# Sheet1.net
KiCad netlist of a schematic drawn in Altium Designer
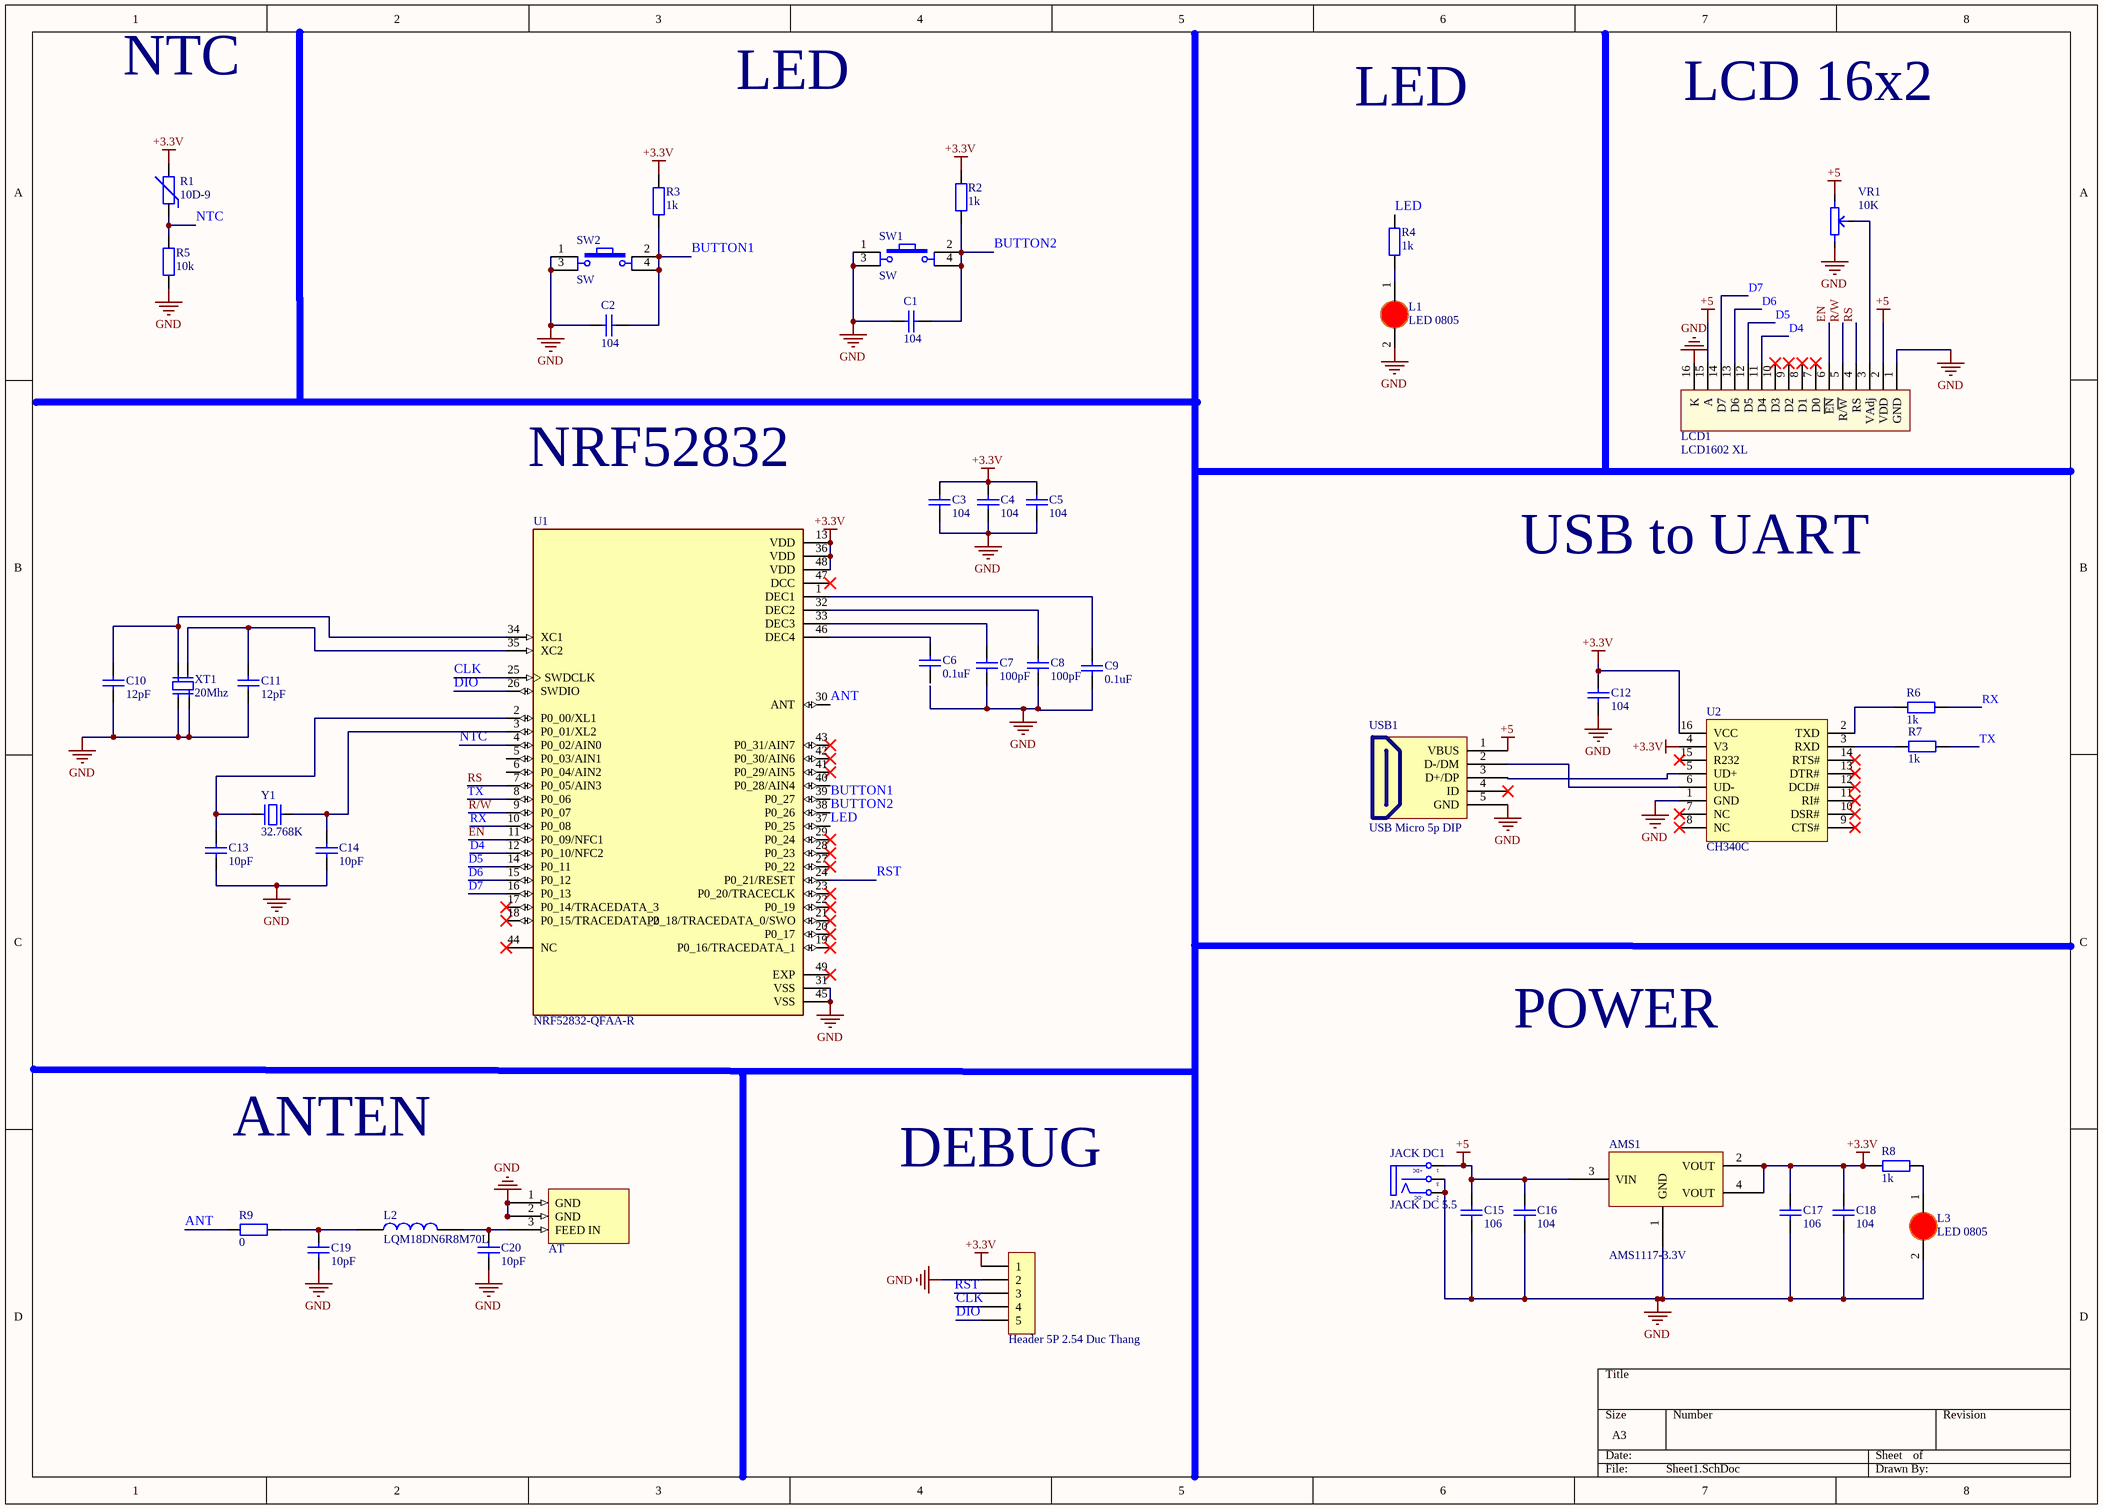
[diagram p0: Sheet1.SchDoc]

(export (version "E")
  (design (tool "Eeschema 10.0.6"))
  (components
    (comp (ref "AMS1")
      (value "AMS1117-3.3V")
      (footprint "SOT223")
      (description "Dán")
      (libsource (lib "Altium_Lib_by_KhueNguyenCreator") (part "AMS1117 SMD"))
    )
    (comp (ref "AT")
      (value "ANTEN")
      (footprint "Anten IFA")
      (description "Anten IFA- BLE RANGDONG")
      (libsource (lib "Altium_Lib_by_KhueNguyenCreator") (part "ANTEN"))
    )
    (comp (ref "C1")
      (value "104")
      (footprint "tu 0603")
      (description "Dán")
      (libsource (lib "Altium_Lib_by_KhueNguyenCreator") (part "Tu 0603 102 50V 10%"))
    )
    (comp (ref "C2")
      (value "104")
      (footprint "tu 0603")
      (description "Dán")
      (libsource (lib "Altium_Lib_by_KhueNguyenCreator") (part "Tu 0603 102 50V 10%"))
    )
    (comp (ref "C3")
      (value "104")
      (footprint "tu 0603")
      (description "Dán")
      (libsource (lib "Altium_Lib_by_KhueNguyenCreator") (part "Tu 0603 102 50V 10%"))
    )
    (comp (ref "C4")
      (value "104")
      (footprint "tu 0603")
      (description "Dán")
      (libsource (lib "Altium_Lib_by_KhueNguyenCreator") (part "Tu 0603 102 50V 10%"))
    )
    (comp (ref "C5")
      (value "104")
      (footprint "tu 0603")
      (description "Dán")
      (libsource (lib "Altium_Lib_by_KhueNguyenCreator") (part "Tu 0603 102 50V 10%"))
    )
    (comp (ref "C6")
      (value "0.1uF")
      (footprint "tu 0603")
      (description "Dán")
      (libsource (lib "Altium_Lib_by_KhueNguyenCreator") (part "Tu 0603 102 50V 10%"))
    )
    (comp (ref "C7")
      (value "100pF")
      (footprint "tu 0603")
      (description "Dán")
      (libsource (lib "Altium_Lib_by_KhueNguyenCreator") (part "Tu 0603 102 50V 10%"))
    )
    (comp (ref "C8")
      (value "100pF")
      (footprint "tu 0603")
      (description "Dán")
      (libsource (lib "Altium_Lib_by_KhueNguyenCreator") (part "Tu 0603 102 50V 10%"))
    )
    (comp (ref "C9")
      (value "0.1uF")
      (footprint "tu 0603")
      (description "Dán")
      (libsource (lib "Altium_Lib_by_KhueNguyenCreator") (part "Tu 0603 102 50V 10%"))
    )
    (comp (ref "C10")
      (value "12pF")
      (footprint "tu 0603")
      (description "Dán")
      (libsource (lib "Altium_Lib_by_KhueNguyenCreator") (part "Tu 0603 102 50V 10%"))
    )
    (comp (ref "C11")
      (value "12pF")
      (footprint "tu 0603")
      (description "Dán")
      (libsource (lib "Altium_Lib_by_KhueNguyenCreator") (part "Tu 0603 102 50V 10%"))
    )
    (comp (ref "C12")
      (value "104")
      (footprint "tu 0603")
      (description "Dán")
      (libsource (lib "Altium_Lib_by_KhueNguyenCreator") (part "Tu 0603 104 50V 10%"))
    )
    (comp (ref "C13")
      (value "10pF")
      (footprint "tu 0603")
      (description "Dán")
      (libsource (lib "Altium_Lib_by_KhueNguyenCreator") (part "Tu 0603 102 50V 10%"))
    )
    (comp (ref "C14")
      (value "10pF")
      (footprint "tu 0603")
      (description "Dán")
      (libsource (lib "Altium_Lib_by_KhueNguyenCreator") (part "Tu 0603 102 50V 10%"))
    )
    (comp (ref "C15")
      (value "106")
      (footprint "tu 0603")
      (description "Dán")
      (libsource (lib "Altium_Lib_by_KhueNguyenCreator") (part "Tu 0603 106 16V 20%"))
    )
    (comp (ref "C16")
      (value "104")
      (footprint "tu 0603")
      (description "Dán")
      (libsource (lib "Altium_Lib_by_KhueNguyenCreator") (part "Tu 0603 104 50V 10%"))
    )
    (comp (ref "C17")
      (value "106")
      (footprint "tu 0603")
      (description "Dán")
      (libsource (lib "Altium_Lib_by_KhueNguyenCreator") (part "Tu 0603 106 16V 20%"))
    )
    (comp (ref "C18")
      (value "104")
      (footprint "tu 0603")
      (description "Dán")
      (libsource (lib "Altium_Lib_by_KhueNguyenCreator") (part "Tu 0603 104 50V 10%"))
    )
    (comp (ref "C19")
      (value "10pF")
      (footprint "tu 0603")
      (description "Dán")
      (libsource (lib "Altium_Lib_by_KhueNguyenCreator") (part "Tu 0603 102 50V 10%"))
    )
    (comp (ref "C20")
      (value "10pF")
      (footprint "tu 0603")
      (description "Dán")
      (libsource (lib "Altium_Lib_by_KhueNguyenCreator") (part "Tu 0603 102 50V 10%"))
    )
    (comp (ref "H1")
      (value "Header 5P 2.54 Duc Thang")
      (footprint "XH2.54M-5")
      (description "Cắm")
      (libsource (lib "Altium_Lib_by_KhueNguyenCreator") (part "Header 5P 2.54 Duc Thang"))
    )
    (comp (ref "JACK DC1")
      (value "JACK DC 5.5")
      (footprint "JACK DC 5.5")
      (libsource (lib "Altium_Lib_by_KhueNguyenCreator") (part "JACK DC 5.5"))
    )
    (comp (ref "L1")
      (value "LED 0805")
      (footprint "LED-0805-Red")
      (description "Dán")
      (libsource (lib "Altium_Lib_by_KhueNguyenCreator") (part "LED 0805 Do"))
    )
    (comp (ref "L2")
      (value "LQM18DN6R8M70L")
      (footprint "INDC1608X95N")
      (description "Inductor with Inductance 6.8uH Tol.+/-20% Package 0603 (1608)")
      (fields (field (name "MF") "Murata Electronics"))
      (libsource (lib "cuon_cam_0603") (part "LQM18DN6R8M70L"))
    )
    (comp (ref "L3")
      (value "LED 0805")
      (footprint "LED-0805-Red")
      (description "Dán")
      (libsource (lib "Altium_Lib_by_KhueNguyenCreator") (part "LED 0805 Do"))
    )
    (comp (ref "LCD1")
      (value "LCD1602 XL")
      (footprint "LCD1602 with Jump")
      (description "LCD 1602 Xanh Lá")
      (libsource (lib "Altium_Lib_by_KhueNguyenCreator") (part "LCD1602 XL"))
    )
    (comp (ref "R1")
      (value "10D-9")
      (footprint "tro nhiet d-9")
      (description "Cắm")
      (libsource (lib "Altium_Lib_by_KhueNguyenCreator") (part "Tro Nhiet NTC 10D-9"))
    )
    (comp (ref "R2")
      (value "1k")
      (footprint "tro smd 0603")
      (description "Dán")
      (libsource (lib "Altium_Lib_by_KhueNguyenCreator") (part "Tro 0603 1% 1k"))
    )
    (comp (ref "R3")
      (value "1k")
      (footprint "tro smd 0603")
      (description "Dán")
      (libsource (lib "Altium_Lib_by_KhueNguyenCreator") (part "Tro 0603 1% 1k"))
    )
    (comp (ref "R4")
      (value "1k")
      (footprint "tro smd 0603")
      (description "Dán")
      (libsource (lib "Altium_Lib_by_KhueNguyenCreator") (part "Tro 0603 1% 1k"))
    )
    (comp (ref "R5")
      (value "10k")
      (footprint "tro smd 0603")
      (description "Dán")
      (libsource (lib "Altium_Lib_by_KhueNguyenCreator") (part "Tro 0603 1% 1k"))
    )
    (comp (ref "R6")
      (value "1k")
      (footprint "tro smd 0603")
      (description "Dán")
      (libsource (lib "Altium_Lib_by_KhueNguyenCreator") (part "Tro 0603 1% 1k"))
    )
    (comp (ref "R7")
      (value "1k")
      (footprint "tro smd 0603")
      (description "Dán")
      (libsource (lib "Altium_Lib_by_KhueNguyenCreator") (part "Tro 0603 1% 1k"))
    )
    (comp (ref "R8")
      (value "1k")
      (footprint "tro smd 0603")
      (description "Dán")
      (libsource (lib "Altium_Lib_by_KhueNguyenCreator") (part "Tro 0603 1% 1k"))
    )
    (comp (ref "R9")
      (value "0")
      (footprint "tro smd 0603")
      (description "Dán")
      (libsource (lib "Altium_Lib_by_KhueNguyenCreator") (part "Tro 0603 1% 1k"))
    )
    (comp (ref "SW1")
      (value "SW")
      (footprint "SW4")
      (description "Switch button 4 pin")
      (libsource (lib "syhaunguyen") (part "SW4"))
    )
    (comp (ref "SW2")
      (value "SW")
      (footprint "SW4")
      (description "Switch button 4 pin")
      (libsource (lib "syhaunguyen") (part "SW4"))
    )
    (comp (ref "U1")
      (value "NRF52832-QFAA-R")
      (footprint "QFN40P600X600X90-49N")
      (description "IC RF TxRx + MCU Bluetooth, General ISM > 1GHz ANT, Bluetooth v5.0 2.4GHz 48-VFQFN Exposed Pad")
      (fields (field (name "MF") "Nordic"))
      (libsource (lib "NRF52832-QFAA-R") (part "NRF52832-QFAA-R"))
    )
    (comp (ref "U2")
      (value "CH340C")
      (footprint "SOIC16_50_284_25X90_SMT")
      (description "USB Bridge, USB to UART USB 2.0 UART Interface")
      (fields (field (name "MANUFACTURER") "Olimex"))
      (libsource (lib "Altium_Lib_by_KhueNguyenCreator") (part "CH340C"))
    )
    (comp (ref "USB1")
      (value "USB Micro 5p DIP")
      (footprint "USB Micro 5p DIP")
      (description "USB Type B")
      (libsource (lib "Altium_Lib_by_KhueNguyenCreator") (part "USB Micro 5p DIP"))
    )
    (comp (ref "VR1")
      (value "10K")
      (footprint "Bien Tro Tam Giac Dung")
      (description "Cắm")
      (libsource (lib "Altium_Lib_by_KhueNguyenCreator") (part "Bien tro tam giac 10K Dung"))
    )
    (comp (ref "XT1")
      (value "20Mhz")
      (footprint "Thach Anh 4 chan 1")
      (description "Crystal For all Crystal 2pin.")
      (libsource (lib "Altium_Lib_by_KhueNguyenCreator") (part "Thach Anh 4 Chan SMD"))
    )
    (comp (ref "Y1")
      (value "32.768K")
      (footprint "Thach Anh 2 chan SMD5032")
      (description "Crystal For all Crystal 2pin.")
      (libsource (lib "Altium_Lib_by_KhueNguyenCreator") (part "Thach Anh 2 chan SMD 5032"))
    )
  )
  (nets
    (net (code "1") (name "+3.3V") (class "Default")
      (node (ref "AMS1") (pin "2") (pinfunction "VOUT_2") (pintype "passive"))
      (node (ref "AMS1") (pin "4") (pinfunction "VOUT_4") (pintype "passive"))
      (node (ref "C12") (pin "1") (pinfunction "1_1") (pintype "passive"))
      (node (ref "C17") (pin "1") (pinfunction "1_1") (pintype "passive"))
      (node (ref "C18") (pin "1") (pinfunction "1_1") (pintype "passive"))
      (node (ref "C3") (pin "1") (pinfunction "1_1") (pintype "passive"))
      (node (ref "C4") (pin "1") (pinfunction "1_1") (pintype "passive"))
      (node (ref "C5") (pin "1") (pinfunction "1_1") (pintype "passive"))
      (node (ref "H1") (pin "1") (pinfunction "1_1") (pintype "passive"))
      (node (ref "R1") (pin "2") (pinfunction "2_2") (pintype "passive"))
      (node (ref "R2") (pin "2") (pinfunction "2_2") (pintype "passive"))
      (node (ref "R3") (pin "2") (pinfunction "2_2") (pintype "passive"))
      (node (ref "R8") (pin "1") (pinfunction "1_1") (pintype "passive"))
      (node (ref "U1") (pin "13") (pinfunction "VDD_13") (pintype "power_in"))
      (node (ref "U1") (pin "36") (pinfunction "VDD_36") (pintype "power_in"))
      (node (ref "U1") (pin "48") (pinfunction "VDD_48") (pintype "power_in"))
      (node (ref "U2") (pin "16") (pinfunction "VCC_16") (pintype "passive"))
      (node (ref "U2") (pin "4") (pinfunction "V3_4") (pintype "passive"))
    )
    (net (code "2") (name "+5") (class "Default")
      (node (ref "AMS1") (pin "3") (pinfunction "VIN_3") (pintype "passive"))
      (node (ref "C15") (pin "1") (pinfunction "1_1") (pintype "passive"))
      (node (ref "C16") (pin "1") (pinfunction "1_1") (pintype "passive"))
      (node (ref "JACK DC1") (pin "1") (pinfunction "T_1") (pintype "passive"))
      (node (ref "LCD1") (pin "15") (pinfunction "A_15") (pintype "passive"))
      (node (ref "LCD1") (pin "2") (pinfunction "VDD_2") (pintype "passive"))
      (node (ref "USB1") (pin "1") (pinfunction "VBUS_1") (pintype "passive"))
      (node (ref "VR1") (pin "1") (pinfunction "1_1") (pintype "passive"))
    )
    (net (code "3") (name "/ANT") (class "Default")
      (node (ref "R9") (pin "1") (pinfunction "1_1") (pintype "passive"))
      (node (ref "U1") (pin "30") (pinfunction "ANT_30") (pintype "bidirectional"))
    )
    (net (code "4") (name "/BUTTON1") (class "Default")
      (node (ref "C2") (pin "2") (pinfunction "2_2") (pintype "passive"))
      (node (ref "R3") (pin "1") (pinfunction "1_1") (pintype "passive"))
      (node (ref "SW2") (pin "2") (pintype "passive"))
      (node (ref "SW2") (pin "4") (pintype "passive"))
      (node (ref "U1") (pin "39") (pinfunction "P0_27_39") (pintype "bidirectional"))
    )
    (net (code "5") (name "/BUTTON2") (class "Default")
      (node (ref "C1") (pin "2") (pinfunction "2_2") (pintype "passive"))
      (node (ref "R2") (pin "1") (pinfunction "1_1") (pintype "passive"))
      (node (ref "SW1") (pin "2") (pintype "passive"))
      (node (ref "SW1") (pin "4") (pintype "passive"))
      (node (ref "U1") (pin "38") (pinfunction "P0_26_38") (pintype "bidirectional"))
    )
    (net (code "6") (name "/CLK") (class "Default")
      (node (ref "H1") (pin "4") (pinfunction "4_4") (pintype "passive"))
      (node (ref "U1") (pin "25") (pinfunction "SWDCLK_25") (pintype "input"))
    )
    (net (code "7") (name "/D4") (class "Default")
      (node (ref "LCD1") (pin "11") (pinfunction "D4_11") (pintype "passive"))
      (node (ref "U1") (pin "12") (pinfunction "P0_10/NFC2_12") (pintype "bidirectional"))
    )
    (net (code "8") (name "/D5") (class "Default")
      (node (ref "LCD1") (pin "12") (pinfunction "D5_12") (pintype "passive"))
      (node (ref "U1") (pin "14") (pinfunction "P0_11_14") (pintype "bidirectional"))
    )
    (net (code "9") (name "/D6") (class "Default")
      (node (ref "LCD1") (pin "13") (pinfunction "D6_13") (pintype "passive"))
      (node (ref "U1") (pin "15") (pinfunction "P0_12_15") (pintype "bidirectional"))
    )
    (net (code "10") (name "/D7") (class "Default")
      (node (ref "LCD1") (pin "14") (pinfunction "D7_14") (pintype "passive"))
      (node (ref "U1") (pin "16") (pinfunction "P0_13_16") (pintype "bidirectional"))
    )
    (net (code "11") (name "/DIO") (class "Default")
      (node (ref "H1") (pin "5") (pinfunction "5_5") (pintype "passive"))
      (node (ref "U1") (pin "26") (pinfunction "SWDIO_26") (pintype "bidirectional"))
    )
    (net (code "12") (name "/EN") (class "Default")
      (node (ref "LCD1") (pin "6") (pinfunction "~{EN}_6") (pintype "passive"))
      (node (ref "U1") (pin "11") (pinfunction "P0_09/NFC1_11") (pintype "bidirectional"))
    )
    (net (code "13") (name "/LED") (class "Default")
      (node (ref "R4") (pin "2") (pinfunction "2_2") (pintype "passive"))
      (node (ref "U1") (pin "37") (pinfunction "P0_25_37") (pintype "bidirectional"))
    )
    (net (code "14") (name "/NTC") (class "Default")
      (node (ref "R1") (pin "1") (pinfunction "1_1") (pintype "passive"))
      (node (ref "R5") (pin "2") (pinfunction "2_2") (pintype "passive"))
      (node (ref "U1") (pin "4") (pinfunction "P0_02/AIN0_4") (pintype "bidirectional"))
    )
    (net (code "15") (name "/RS") (class "Default")
      (node (ref "LCD1") (pin "4") (pinfunction "RS_4") (pintype "passive"))
      (node (ref "U1") (pin "7") (pinfunction "P0_05/AIN3_7") (pintype "bidirectional"))
    )
    (net (code "16") (name "/RST") (class "Default")
      (node (ref "H1") (pin "3") (pinfunction "3_3") (pintype "passive"))
      (node (ref "U1") (pin "24") (pinfunction "P0_21/RESET_24") (pintype "bidirectional"))
    )
    (net (code "17") (name "/RX") (class "Default")
      (node (ref "R6") (pin "2") (pinfunction "2_2") (pintype "passive"))
      (node (ref "U1") (pin "10") (pinfunction "P0_08_10") (pintype "bidirectional"))
    )
    (net (code "18") (name "/R{slash}W") (class "Default")
      (node (ref "LCD1") (pin "5") (pinfunction "R/~{W}_5") (pintype "passive"))
      (node (ref "U1") (pin "9") (pinfunction "P0_07_9") (pintype "bidirectional"))
    )
    (net (code "19") (name "/TX") (class "Default")
      (node (ref "R7") (pin "2") (pinfunction "2_2") (pintype "passive"))
      (node (ref "U1") (pin "8") (pinfunction "P0_06_8") (pintype "bidirectional"))
    )
    (net (code "20") (name "GND") (class "Default")
      (node (ref "AMS1") (pin "1") (pinfunction "GND_1") (pintype "passive"))
      (node (ref "AT") (pin "1") (pinfunction "GND_1") (pintype "input"))
      (node (ref "AT") (pin "2") (pinfunction "GND_2") (pintype "input"))
      (node (ref "C1") (pin "1") (pinfunction "1_1") (pintype "passive"))
      (node (ref "C10") (pin "2") (pinfunction "2_2") (pintype "passive"))
      (node (ref "C11") (pin "2") (pinfunction "2_2") (pintype "passive"))
      (node (ref "C12") (pin "2") (pinfunction "2_2") (pintype "passive"))
      (node (ref "C13") (pin "2") (pinfunction "2_2") (pintype "passive"))
      (node (ref "C14") (pin "2") (pinfunction "2_2") (pintype "passive"))
      (node (ref "C15") (pin "2") (pinfunction "2_2") (pintype "passive"))
      (node (ref "C16") (pin "2") (pinfunction "2_2") (pintype "passive"))
      (node (ref "C17") (pin "2") (pinfunction "2_2") (pintype "passive"))
      (node (ref "C18") (pin "2") (pinfunction "2_2") (pintype "passive"))
      (node (ref "C19") (pin "2") (pinfunction "2_2") (pintype "passive"))
      (node (ref "C2") (pin "1") (pinfunction "1_1") (pintype "passive"))
      (node (ref "C20") (pin "2") (pinfunction "2_2") (pintype "passive"))
      (node (ref "C3") (pin "2") (pinfunction "2_2") (pintype "passive"))
      (node (ref "C4") (pin "2") (pinfunction "2_2") (pintype "passive"))
      (node (ref "C5") (pin "2") (pinfunction "2_2") (pintype "passive"))
      (node (ref "C7") (pin "2") (pinfunction "2_2") (pintype "passive"))
      (node (ref "C8") (pin "2") (pinfunction "2_2") (pintype "passive"))
      (node (ref "C9") (pin "2") (pinfunction "2_2") (pintype "passive"))
      (node (ref "H1") (pin "2") (pinfunction "2_2") (pintype "passive"))
      (node (ref "JACK DC1") (pin "2") (pinfunction "TN_2") (pintype "passive"))
      (node (ref "JACK DC1") (pin "3") (pinfunction "S_3") (pintype "power_in"))
      (node (ref "L1") (pin "2") (pinfunction "K_2") (pintype "passive"))
      (node (ref "L3") (pin "2") (pinfunction "K_2") (pintype "passive"))
      (node (ref "LCD1") (pin "1") (pinfunction "GND_1") (pintype "passive"))
      (node (ref "LCD1") (pin "16") (pinfunction "K_16") (pintype "passive"))
      (node (ref "R5") (pin "1") (pinfunction "1_1") (pintype "passive"))
      (node (ref "SW1") (pin "1") (pintype "passive"))
      (node (ref "SW1") (pin "3") (pintype "passive"))
      (node (ref "SW2") (pin "1") (pintype "passive"))
      (node (ref "SW2") (pin "3") (pintype "passive"))
      (node (ref "U1") (pin "31") (pinfunction "VSS_31") (pintype "power_in"))
      (node (ref "U1") (pin "45") (pinfunction "VSS_45") (pintype "power_in"))
      (node (ref "U2") (pin "1") (pinfunction "GND_1") (pintype "passive"))
      (node (ref "USB1") (pin "5") (pinfunction "GND_5") (pintype "passive"))
      (node (ref "VR1") (pin "3") (pinfunction "3_3") (pintype "passive"))
      (node (ref "XT1") (pin "1") (pinfunction "1_1") (pintype "passive"))
      (node (ref "XT1") (pin "3") (pinfunction "3_3") (pintype "passive"))
    )
    (net (code "21") (name "Net-(AT-FEED_IN)") (class "Default")
      (node (ref "AT") (pin "3") (pinfunction "FEED_IN_3") (pintype "input"))
      (node (ref "C20") (pin "1") (pinfunction "1_1") (pintype "passive"))
      (node (ref "L2") (pin "2") (pinfunction "2_2") (pintype "passive"))
    )
    (net (code "22") (name "Net-(C19-Pad1)") (class "Default")
      (node (ref "C19") (pin "1") (pinfunction "1_1") (pintype "passive"))
      (node (ref "L2") (pin "1") (pinfunction "1_1") (pintype "passive"))
      (node (ref "R9") (pin "2") (pinfunction "2_2") (pintype "passive"))
    )
    (net (code "23") (name "Net-(L1-A)") (class "Default")
      (node (ref "L1") (pin "1") (pinfunction "A_1") (pintype "passive"))
      (node (ref "R4") (pin "1") (pinfunction "1_1") (pintype "passive"))
    )
    (net (code "24") (name "Net-(L3-A)") (class "Default")
      (node (ref "L3") (pin "1") (pinfunction "A_1") (pintype "passive"))
      (node (ref "R8") (pin "2") (pinfunction "2_2") (pintype "passive"))
    )
    (net (code "25") (name "Net-(LCD1-VAdj)") (class "Default")
      (node (ref "LCD1") (pin "3") (pinfunction "VAdj_3") (pintype "passive"))
      (node (ref "VR1") (pin "2") (pinfunction "2_2") (pintype "passive"))
    )
    (net (code "26") (name "Net-(U1-DEC1)") (class "Default")
      (node (ref "C9") (pin "1") (pinfunction "1_1") (pintype "passive"))
      (node (ref "U1") (pin "1") (pinfunction "DEC1_1") (pintype "power_in"))
    )
    (net (code "27") (name "Net-(U1-DEC2)") (class "Default")
      (node (ref "C8") (pin "1") (pinfunction "1_1") (pintype "passive"))
      (node (ref "U1") (pin "32") (pinfunction "DEC2_32") (pintype "power_in"))
    )
    (net (code "28") (name "Net-(U1-DEC3)") (class "Default")
      (node (ref "C7") (pin "1") (pinfunction "1_1") (pintype "passive"))
      (node (ref "U1") (pin "33") (pinfunction "DEC3_33") (pintype "power_in"))
    )
    (net (code "29") (name "Net-(U1-DEC4)") (class "Default")
      (node (ref "C6") (pin "1") (pinfunction "1_1") (pintype "passive"))
      (node (ref "U1") (pin "46") (pinfunction "DEC4_46") (pintype "power_in"))
    )
    (net (code "30") (name "Net-(U1-P0_00{slash}XL1)") (class "Default")
      (node (ref "C13") (pin "1") (pinfunction "1_1") (pintype "passive"))
      (node (ref "U1") (pin "2") (pinfunction "P0_00/XL1_2") (pintype "bidirectional"))
      (node (ref "Y1") (pin "1") (pinfunction "1_1") (pintype "passive"))
    )
    (net (code "31") (name "Net-(U1-P0_01{slash}XL2)") (class "Default")
      (node (ref "C14") (pin "1") (pinfunction "1_1") (pintype "passive"))
      (node (ref "U1") (pin "3") (pinfunction "P0_01/XL2_3") (pintype "bidirectional"))
      (node (ref "Y1") (pin "2") (pinfunction "2_2") (pintype "passive"))
    )
    (net (code "32") (name "Net-(U1-XC1)") (class "Default")
      (node (ref "C10") (pin "1") (pinfunction "1_1") (pintype "passive"))
      (node (ref "U1") (pin "34") (pinfunction "XC1_34") (pintype "input"))
      (node (ref "XT1") (pin "2") (pinfunction "2_2") (pintype "passive"))
    )
    (net (code "33") (name "Net-(U1-XC2)") (class "Default")
      (node (ref "C11") (pin "1") (pinfunction "1_1") (pintype "passive"))
      (node (ref "U1") (pin "35") (pinfunction "XC2_35") (pintype "input"))
      (node (ref "XT1") (pin "4") (pinfunction "4_4") (pintype "passive"))
    )
    (net (code "34") (name "Net-(U2-RXD)") (class "Default")
      (node (ref "R7") (pin "1") (pinfunction "1_1") (pintype "passive"))
      (node (ref "U2") (pin "3") (pinfunction "RXD_3") (pintype "passive"))
    )
    (net (code "35") (name "Net-(U2-TXD)") (class "Default")
      (node (ref "R6") (pin "1") (pinfunction "1_1") (pintype "passive"))
      (node (ref "U2") (pin "2") (pinfunction "TXD_2") (pintype "passive"))
    )
    (net (code "36") (name "Net-(U2-UD+)") (class "Default")
      (node (ref "U2") (pin "5") (pinfunction "UD+_5") (pintype "passive"))
      (node (ref "USB1") (pin "3") (pinfunction "D+/DP_3") (pintype "passive"))
    )
    (net (code "37") (name "Net-(U2-UD-)") (class "Default")
      (node (ref "U2") (pin "6") (pinfunction "UD-_6") (pintype "passive"))
      (node (ref "USB1") (pin "2") (pinfunction "D-/DM_2") (pintype "passive"))
    )
    (net (code "38") (name "unconnected-(C6-Pad2)") (class "Default")
      (node (ref "C6") (pin "2") (pinfunction "2_2") (pintype "passive"))
    )
    (net (code "39") (name "unconnected-(LCD1-D0-Pad7)") (class "Default")
      (node (ref "LCD1") (pin "7") (pinfunction "D0_7") (pintype "passive+no_connect"))
    )
    (net (code "40") (name "unconnected-(LCD1-D1-Pad8)") (class "Default")
      (node (ref "LCD1") (pin "8") (pinfunction "D1_8") (pintype "passive+no_connect"))
    )
    (net (code "41") (name "unconnected-(LCD1-D2-Pad9)") (class "Default")
      (node (ref "LCD1") (pin "9") (pinfunction "D2_9") (pintype "passive+no_connect"))
    )
    (net (code "42") (name "unconnected-(LCD1-D3-Pad10)") (class "Default")
      (node (ref "LCD1") (pin "10") (pinfunction "D3_10") (pintype "passive+no_connect"))
    )
    (net (code "43") (name "unconnected-(U1-DCC-Pad47)") (class "Default")
      (node (ref "U1") (pin "47") (pinfunction "DCC_47") (pintype "power_in+no_connect"))
    )
    (net (code "44") (name "unconnected-(U1-EXP-Pad49)") (class "Default")
      (node (ref "U1") (pin "49") (pinfunction "EXP_49") (pintype "power_in+no_connect"))
    )
    (net (code "45") (name "unconnected-(U1-NC-Pad44)") (class "Default")
      (node (ref "U1") (pin "44") (pinfunction "NC_44") (pintype "passive+no_connect"))
    )
    (net (code "46") (name "unconnected-(U1-P0_03{slash}AIN1-Pad5)") (class "Default")
      (node (ref "U1") (pin "5") (pinfunction "P0_03/AIN1_5") (pintype "bidirectional"))
    )
    (net (code "47") (name "unconnected-(U1-P0_04{slash}AIN2-Pad6)") (class "Default")
      (node (ref "U1") (pin "6") (pinfunction "P0_04/AIN2_6") (pintype "bidirectional"))
    )
    (net (code "48") (name "unconnected-(U1-P0_14{slash}TRACEDATA_3-Pad17)") (class "Default")
      (node (ref "U1") (pin "17") (pinfunction "P0_14/TRACEDATA_3_17") (pintype "bidirectional+no_connect"))
    )
    (net (code "49") (name "unconnected-(U1-P0_15{slash}TRACEDATA_2-Pad18)") (class "Default")
      (node (ref "U1") (pin "18") (pinfunction "P0_15/TRACEDATA_2_18") (pintype "bidirectional+no_connect"))
    )
    (net (code "50") (name "unconnected-(U1-P0_16{slash}TRACEDATA_1-Pad19)") (class "Default")
      (node (ref "U1") (pin "19") (pinfunction "P0_16/TRACEDATA_1_19") (pintype "bidirectional+no_connect"))
    )
    (net (code "51") (name "unconnected-(U1-P0_17-Pad20)") (class "Default")
      (node (ref "U1") (pin "20") (pinfunction "P0_17_20") (pintype "bidirectional+no_connect"))
    )
    (net (code "52") (name "unconnected-(U1-P0_18{slash}TRACEDATA_0{slash}SWO-Pad21)") (class "Default")
      (node (ref "U1") (pin "21") (pinfunction "P0_18/TRACEDATA_0/SWO_21") (pintype "bidirectional+no_connect"))
    )
    (net (code "53") (name "unconnected-(U1-P0_19-Pad22)") (class "Default")
      (node (ref "U1") (pin "22") (pinfunction "P0_19_22") (pintype "bidirectional+no_connect"))
    )
    (net (code "54") (name "unconnected-(U1-P0_20{slash}TRACECLK-Pad23)") (class "Default")
      (node (ref "U1") (pin "23") (pinfunction "P0_20/TRACECLK_23") (pintype "bidirectional+no_connect"))
    )
    (net (code "55") (name "unconnected-(U1-P0_22-Pad27)") (class "Default")
      (node (ref "U1") (pin "27") (pinfunction "P0_22_27") (pintype "bidirectional+no_connect"))
    )
    (net (code "56") (name "unconnected-(U1-P0_23-Pad28)") (class "Default")
      (node (ref "U1") (pin "28") (pinfunction "P0_23_28") (pintype "bidirectional+no_connect"))
    )
    (net (code "57") (name "unconnected-(U1-P0_24-Pad29)") (class "Default")
      (node (ref "U1") (pin "29") (pinfunction "P0_24_29") (pintype "bidirectional+no_connect"))
    )
    (net (code "58") (name "unconnected-(U1-P0_28{slash}AIN4-Pad40)") (class "Default")
      (node (ref "U1") (pin "40") (pinfunction "P0_28/AIN4_40") (pintype "bidirectional"))
    )
    (net (code "59") (name "unconnected-(U1-P0_29{slash}AIN5-Pad41)") (class "Default")
      (node (ref "U1") (pin "41") (pinfunction "P0_29/AIN5_41") (pintype "bidirectional+no_connect"))
    )
    (net (code "60") (name "unconnected-(U1-P0_30{slash}AIN6-Pad42)") (class "Default")
      (node (ref "U1") (pin "42") (pinfunction "P0_30/AIN6_42") (pintype "bidirectional+no_connect"))
    )
    (net (code "61") (name "unconnected-(U1-P0_31{slash}AIN7-Pad43)") (class "Default")
      (node (ref "U1") (pin "43") (pinfunction "P0_31/AIN7_43") (pintype "bidirectional+no_connect"))
    )
    (net (code "62") (name "unconnected-(U2-CTS#-Pad9)") (class "Default")
      (node (ref "U2") (pin "9") (pinfunction "CTS#_9") (pintype "passive+no_connect"))
    )
    (net (code "63") (name "unconnected-(U2-DCD#-Pad12)") (class "Default")
      (node (ref "U2") (pin "12") (pinfunction "DCD#_12") (pintype "passive+no_connect"))
    )
    (net (code "64") (name "unconnected-(U2-DSR#-Pad10)") (class "Default")
      (node (ref "U2") (pin "10") (pinfunction "DSR#_10") (pintype "passive+no_connect"))
    )
    (net (code "65") (name "unconnected-(U2-DTR#-Pad13)") (class "Default")
      (node (ref "U2") (pin "13") (pinfunction "DTR#_13") (pintype "passive+no_connect"))
    )
    (net (code "66") (name "unconnected-(U2-NC-Pad7)") (class "Default")
      (node (ref "U2") (pin "7") (pinfunction "NC_7") (pintype "passive+no_connect"))
    )
    (net (code "67") (name "unconnected-(U2-NC-Pad8)") (class "Default")
      (node (ref "U2") (pin "8") (pinfunction "NC_8") (pintype "passive+no_connect"))
    )
    (net (code "68") (name "unconnected-(U2-R232-Pad15)") (class "Default")
      (node (ref "U2") (pin "15") (pinfunction "R232_15") (pintype "passive+no_connect"))
    )
    (net (code "69") (name "unconnected-(U2-RI#-Pad11)") (class "Default")
      (node (ref "U2") (pin "11") (pinfunction "RI#_11") (pintype "passive+no_connect"))
    )
    (net (code "70") (name "unconnected-(U2-RTS#-Pad14)") (class "Default")
      (node (ref "U2") (pin "14") (pinfunction "RTS#_14") (pintype "passive+no_connect"))
    )
    (net (code "71") (name "unconnected-(USB1-ID-Pad4)") (class "Default")
      (node (ref "USB1") (pin "4") (pinfunction "ID_4") (pintype "passive+no_connect"))
    )
  )
)
